# Motors-power-board.net
KiCad netlist of a schematic drawn in EAGLE
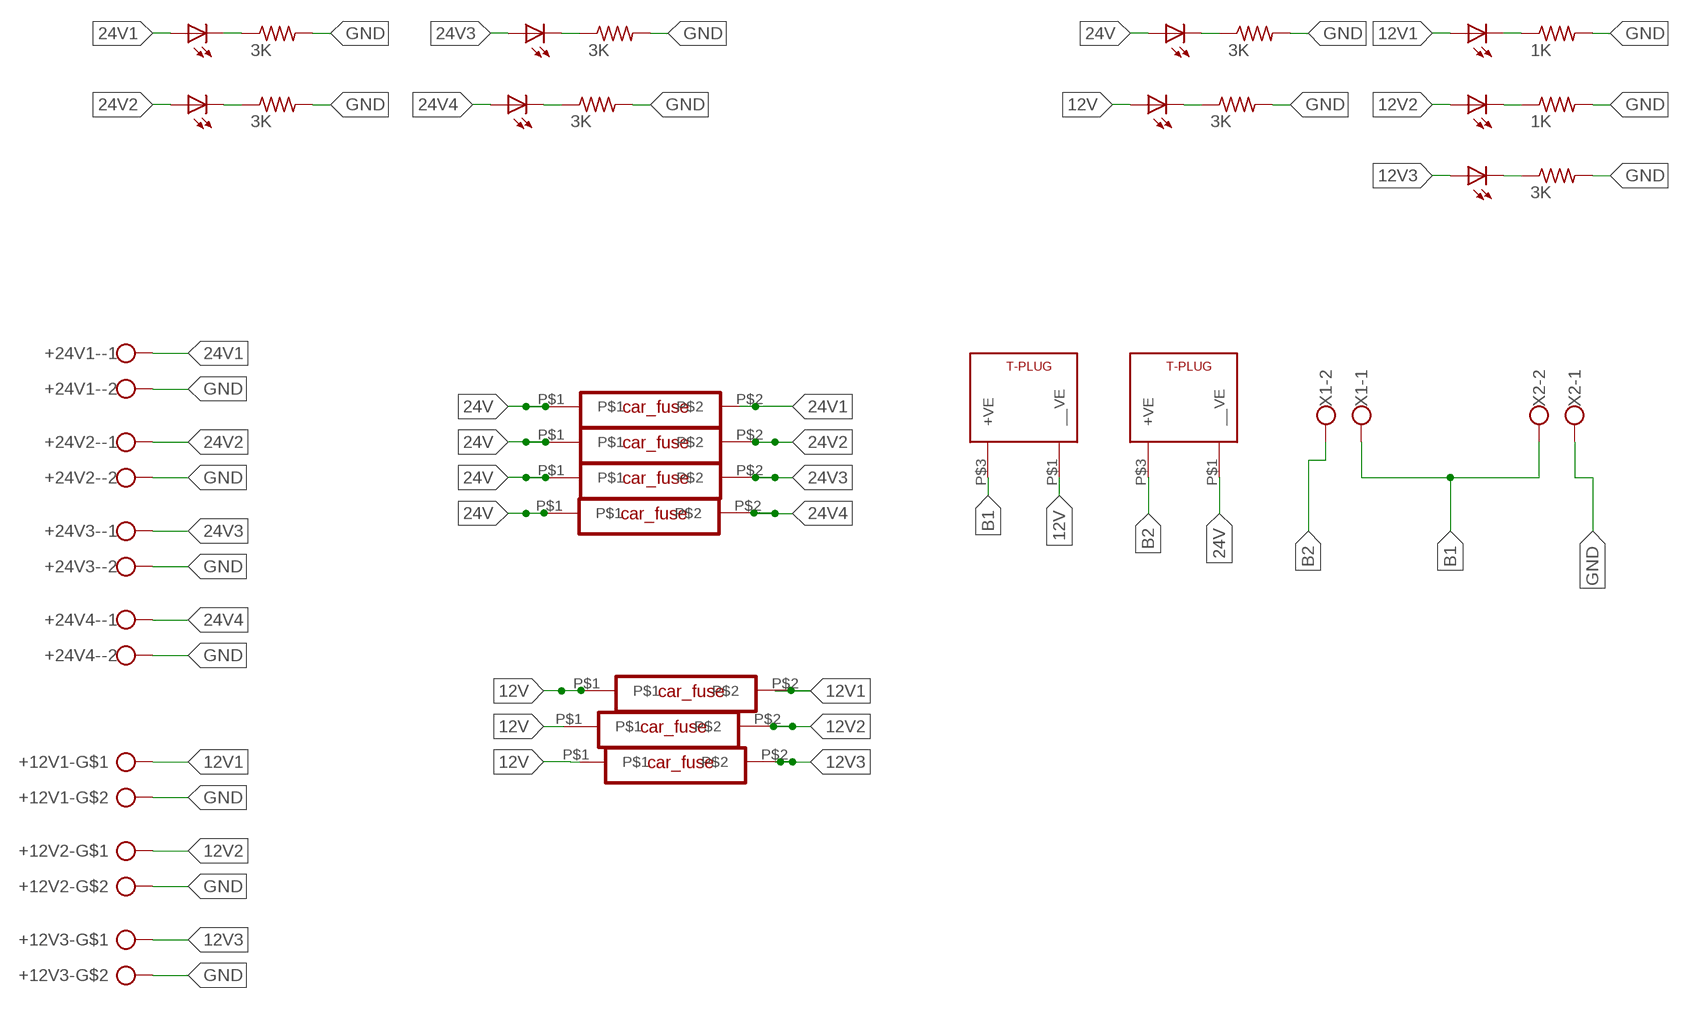
[diagram p0: schematic, sheet 1]

(export (version "E")
  (design (tool "Eeschema 10.0.6"))
  (components
    (comp (ref "+12V1-")
      (value "CON_PTR_2")
      (footprint "eagle-import:AK300_2")
      (libsource (lib "eagle-import") (part "CON_PTR_2"))
    )
    (comp (ref "+12V2-")
      (value "CON_PTR_2")
      (footprint "eagle-import:AK300_2")
      (libsource (lib "eagle-import") (part "CON_PTR_2"))
    )
    (comp (ref "+12V3-")
      (value "CON_PTR_2")
      (footprint "eagle-import:AK300_2")
      (libsource (lib "eagle-import") (part "CON_PTR_2"))
    )
    (comp (ref "+24V1-")
      (value "ROSTA.POWER")
      (footprint "eagle-import:W239-302")
      (libsource (lib "eagle-import") (part "ROSTA.POWER"))
    )
    (comp (ref "+24V2-")
      (value "ROSTA.POWER")
      (footprint "eagle-import:W239-302")
      (libsource (lib "eagle-import") (part "ROSTA.POWER"))
    )
    (comp (ref "+24V3-")
      (value "ROSTA.POWER")
      (footprint "eagle-import:W239-302")
      (libsource (lib "eagle-import") (part "ROSTA.POWER"))
    )
    (comp (ref "+24V4-")
      (value "ROSTA.POWER")
      (footprint "eagle-import:W239-302")
      (libsource (lib "eagle-import") (part "ROSTA.POWER"))
    )
    (comp (ref "1K1")
      (value "3K")
      (footprint "eagle-import:0204_7")
      (libsource (lib "eagle-import") (part "RES-7"))
    )
    (comp (ref "1K2")
      (value "1K")
      (footprint "eagle-import:0204_7")
      (libsource (lib "eagle-import") (part "RES-7"))
    )
    (comp (ref "U$4")
      (value "LED24V")
      (footprint "eagle-import:LED3MM")
      (libsource (lib "eagle-import") (part "LED3MM"))
    )
    (comp (ref "U$5")
      (value "T_CONNECTOR")
      (footprint "eagle-import:T-PLUG")
      (libsource (lib "eagle-import") (part "T_CONNECTOR"))
    )
    (comp (ref "U$6")
      (value "T_CONNECTOR")
      (footprint "eagle-import:T-PLUG")
      (libsource (lib "eagle-import") (part "T_CONNECTOR"))
    )
    (comp (ref "U$8")
      (value "3K")
      (footprint "eagle-import:0204_7")
      (libsource (lib "eagle-import") (part "RES-7"))
    )
    (comp (ref "U$9")
      (value "3K")
      (footprint "eagle-import:0204_7")
      (libsource (lib "eagle-import") (part "RES-7"))
    )
    (comp (ref "U$10")
      (value "CAR_FUSE")
      (footprint "eagle-import:CAR_FUSE")
      (libsource (lib "eagle-import") (part "CAR_FUSE"))
    )
    (comp (ref "U$11")
      (value "CAR_FUSE")
      (footprint "eagle-import:CAR_FUSE")
      (libsource (lib "eagle-import") (part "CAR_FUSE"))
    )
    (comp (ref "U$12")
      (value "CAR_FUSE")
      (footprint "eagle-import:CAR_FUSE")
      (libsource (lib "eagle-import") (part "CAR_FUSE"))
    )
    (comp (ref "U$13")
      (value "CAR_FUSE")
      (footprint "eagle-import:CAR_FUSE")
      (libsource (lib "eagle-import") (part "CAR_FUSE"))
    )
    (comp (ref "U$14")
      (value "CAR_FUSE")
      (footprint "eagle-import:CAR_FUSE")
      (libsource (lib "eagle-import") (part "CAR_FUSE"))
    )
    (comp (ref "U$15")
      (value "CAR_FUSE")
      (footprint "eagle-import:CAR_FUSE")
      (libsource (lib "eagle-import") (part "CAR_FUSE"))
    )
    (comp (ref "U$16")
      (value "CAR_FUSE")
      (footprint "eagle-import:CAR_FUSE")
      (libsource (lib "eagle-import") (part "CAR_FUSE"))
    )
    (comp (ref "U$18")
      (value "LED5V2")
      (footprint "eagle-import:LED3MM")
      (libsource (lib "eagle-import") (part "LED3MM"))
    )
    (comp (ref "U$19")
      (value "LED5V1")
      (footprint "eagle-import:LED3MM")
      (libsource (lib "eagle-import") (part "LED3MM"))
    )
    (comp (ref "U$20")
      (value "LED24V")
      (footprint "eagle-import:LED3MM")
      (libsource (lib "eagle-import") (part "LED3MM"))
    )
    (comp (ref "U$21")
      (value "LED12V")
      (footprint "eagle-import:LED3MM")
      (libsource (lib "eagle-import") (part "LED3MM"))
    )
    (comp (ref "U$22")
      (value "3K")
      (footprint "eagle-import:0204_7")
      (libsource (lib "eagle-import") (part "RES-7"))
    )
    (comp (ref "U$23")
      (value "3K")
      (footprint "eagle-import:0204_7")
      (libsource (lib "eagle-import") (part "RES-7"))
    )
    (comp (ref "U$24")
      (value "3K")
      (footprint "eagle-import:0204_7")
      (libsource (lib "eagle-import") (part "RES-7"))
    )
    (comp (ref "U$25")
      (value "LED5V2")
      (footprint "eagle-import:LED3MM")
      (libsource (lib "eagle-import") (part "LED3MM"))
    )
    (comp (ref "U$26")
      (value "LED5V1")
      (footprint "eagle-import:LED3MM")
      (libsource (lib "eagle-import") (part "LED3MM"))
    )
    (comp (ref "U$27")
      (value "LED24V")
      (footprint "eagle-import:LED3MM")
      (libsource (lib "eagle-import") (part "LED3MM"))
    )
    (comp (ref "U$28")
      (value "LED24V")
      (footprint "eagle-import:LED3MM")
      (libsource (lib "eagle-import") (part "LED3MM"))
    )
    (comp (ref "U$29")
      (value "1K")
      (footprint "eagle-import:0204_7")
      (libsource (lib "eagle-import") (part "RES-7"))
    )
    (comp (ref "U$31")
      (value "3K")
      (footprint "eagle-import:0204_7")
      (libsource (lib "eagle-import") (part "RES-7"))
    )
    (comp (ref "X1")
      (value "ROSTA.POWER")
      (footprint "eagle-import:W239-302")
      (libsource (lib "eagle-import") (part "MIA_LIBRARY-2-2-2_16672108_ROSTA.POWER"))
    )
    (comp (ref "X2")
      (value "ROSTA.POWER")
      (footprint "eagle-import:W239-302")
      (libsource (lib "eagle-import") (part "MIA_LIBRARY-2-2-2_16672108_ROSTA.POWER"))
    )
  )
  (nets
    (net (code "1") (name "12V") (class "Default")
      (node (ref "U$14") (pin "P$1") (pinfunction "P$1_P$1") (pintype "bidirectional"))
      (node (ref "U$15") (pin "P$1") (pinfunction "P$1_P$1") (pintype "bidirectional"))
      (node (ref "U$16") (pin "P$1") (pinfunction "P$1_P$1") (pintype "bidirectional"))
      (node (ref "U$28") (pin "A") (pinfunction "A_A") (pintype "passive"))
      (node (ref "U$5") (pin "P$1") (pinfunction "__VE_P$1") (pintype "bidirectional"))
    )
    (net (code "2") (name "12V1") (class "Default")
      (node (ref "+12V1-") (pin "1") (pinfunction "KL_1") (pintype "passive"))
      (node (ref "U$14") (pin "P$2") (pinfunction "P$2_P$2") (pintype "bidirectional"))
      (node (ref "U$25") (pin "A") (pinfunction "A_A") (pintype "passive"))
    )
    (net (code "3") (name "12V2") (class "Default")
      (node (ref "+12V2-") (pin "1") (pinfunction "KL_1") (pintype "passive"))
      (node (ref "U$15") (pin "P$2") (pinfunction "P$2_P$2") (pintype "bidirectional"))
      (node (ref "U$26") (pin "A") (pinfunction "A_A") (pintype "passive"))
    )
    (net (code "4") (name "12V3") (class "Default")
      (node (ref "+12V3-") (pin "1") (pinfunction "KL_1") (pintype "passive"))
      (node (ref "U$16") (pin "P$2") (pinfunction "P$2_P$2") (pintype "bidirectional"))
      (node (ref "U$27") (pin "A") (pinfunction "A_A") (pintype "passive"))
    )
    (net (code "5") (name "24V") (class "Default")
      (node (ref "U$10") (pin "P$1") (pinfunction "P$1_P$1") (pintype "bidirectional"))
      (node (ref "U$11") (pin "P$1") (pinfunction "P$1_P$1") (pintype "bidirectional"))
      (node (ref "U$12") (pin "P$1") (pinfunction "P$1_P$1") (pintype "bidirectional"))
      (node (ref "U$13") (pin "P$1") (pinfunction "P$1_P$1") (pintype "bidirectional"))
      (node (ref "U$4") (pin "A") (pinfunction "A_A") (pintype "passive"))
      (node (ref "U$6") (pin "P$1") (pinfunction "__VE_P$1") (pintype "bidirectional"))
    )
    (net (code "6") (name "24V1") (class "Default")
      (node (ref "+24V1-") (pin "1") (pinfunction "KL_1") (pintype "passive"))
      (node (ref "U$10") (pin "P$2") (pinfunction "P$2_P$2") (pintype "bidirectional"))
      (node (ref "U$18") (pin "A") (pinfunction "A_A") (pintype "passive"))
    )
    (net (code "7") (name "24V2") (class "Default")
      (node (ref "+24V2-") (pin "1") (pinfunction "KL_1") (pintype "passive"))
      (node (ref "U$11") (pin "P$2") (pinfunction "P$2_P$2") (pintype "bidirectional"))
      (node (ref "U$19") (pin "A") (pinfunction "A_A") (pintype "passive"))
    )
    (net (code "8") (name "24V3") (class "Default")
      (node (ref "+24V3-") (pin "1") (pinfunction "KL_1") (pintype "passive"))
      (node (ref "U$12") (pin "P$2") (pinfunction "P$2_P$2") (pintype "bidirectional"))
      (node (ref "U$20") (pin "A") (pinfunction "A_A") (pintype "passive"))
    )
    (net (code "9") (name "24V4") (class "Default")
      (node (ref "+24V4-") (pin "1") (pinfunction "KL_1") (pintype "passive"))
      (node (ref "U$13") (pin "P$2") (pinfunction "P$2_P$2") (pintype "bidirectional"))
      (node (ref "U$21") (pin "A") (pinfunction "A_A") (pintype "passive"))
    )
    (net (code "10") (name "B1") (class "Default")
      (node (ref "U$5") (pin "P$3") (pinfunction "+VE_P$3") (pintype "bidirectional"))
      (node (ref "X1") (pin "1") (pinfunction "KL_1") (pintype "passive"))
      (node (ref "X2") (pin "2") (pinfunction "KL_2") (pintype "passive"))
    )
    (net (code "11") (name "B2") (class "Default")
      (node (ref "U$6") (pin "P$3") (pinfunction "+VE_P$3") (pintype "bidirectional"))
      (node (ref "X1") (pin "2") (pinfunction "KL_2") (pintype "passive"))
    )
    (net (code "12") (name "GND") (class "Default")
      (node (ref "+12V1-") (pin "2") (pinfunction "KL_2") (pintype "passive"))
      (node (ref "+12V2-") (pin "2") (pinfunction "KL_2") (pintype "passive"))
      (node (ref "+12V3-") (pin "2") (pinfunction "KL_2") (pintype "passive"))
      (node (ref "+24V1-") (pin "2") (pinfunction "KL_2") (pintype "passive"))
      (node (ref "+24V2-") (pin "2") (pinfunction "KL_2") (pintype "passive"))
      (node (ref "+24V3-") (pin "2") (pinfunction "KL_2") (pintype "passive"))
      (node (ref "+24V4-") (pin "2") (pinfunction "KL_2") (pintype "passive"))
      (node (ref "1K1") (pin "2") (pinfunction "2_2") (pintype "passive"))
      (node (ref "1K2") (pin "2") (pinfunction "2_2") (pintype "passive"))
      (node (ref "U$22") (pin "2") (pinfunction "2_2") (pintype "passive"))
      (node (ref "U$23") (pin "2") (pinfunction "2_2") (pintype "passive"))
      (node (ref "U$24") (pin "2") (pinfunction "2_2") (pintype "passive"))
      (node (ref "U$29") (pin "2") (pinfunction "2_2") (pintype "passive"))
      (node (ref "U$31") (pin "2") (pinfunction "2_2") (pintype "passive"))
      (node (ref "U$8") (pin "2") (pinfunction "2_2") (pintype "passive"))
      (node (ref "U$9") (pin "2") (pinfunction "2_2") (pintype "passive"))
      (node (ref "X2") (pin "1") (pinfunction "KL_1") (pintype "passive"))
    )
    (net (code "13") (name "Net-(U$4-C)") (class "Default")
      (node (ref "U$4") (pin "K") (pinfunction "C_K") (pintype "passive"))
      (node (ref "U$9") (pin "1") (pinfunction "1_1") (pintype "passive"))
    )
    (net (code "14") (name "Net-(U$18-C)") (class "Default")
      (node (ref "1K1") (pin "1") (pinfunction "1_1") (pintype "passive"))
      (node (ref "U$18") (pin "K") (pinfunction "C_K") (pintype "passive"))
    )
    (net (code "15") (name "Net-(U$19-C)") (class "Default")
      (node (ref "U$19") (pin "K") (pinfunction "C_K") (pintype "passive"))
      (node (ref "U$22") (pin "1") (pinfunction "1_1") (pintype "passive"))
    )
    (net (code "16") (name "Net-(U$20-C)") (class "Default")
      (node (ref "U$20") (pin "K") (pinfunction "C_K") (pintype "passive"))
      (node (ref "U$24") (pin "1") (pinfunction "1_1") (pintype "passive"))
    )
    (net (code "17") (name "Net-(U$21-C)") (class "Default")
      (node (ref "U$21") (pin "K") (pinfunction "C_K") (pintype "passive"))
      (node (ref "U$23") (pin "1") (pinfunction "1_1") (pintype "passive"))
    )
    (net (code "18") (name "Net-(U$25-C)") (class "Default")
      (node (ref "1K2") (pin "1") (pinfunction "1_1") (pintype "passive"))
      (node (ref "U$25") (pin "K") (pinfunction "C_K") (pintype "passive"))
    )
    (net (code "19") (name "Net-(U$26-C)") (class "Default")
      (node (ref "U$26") (pin "K") (pinfunction "C_K") (pintype "passive"))
      (node (ref "U$29") (pin "1") (pinfunction "1_1") (pintype "passive"))
    )
    (net (code "20") (name "Net-(U$27-C)") (class "Default")
      (node (ref "U$27") (pin "K") (pinfunction "C_K") (pintype "passive"))
      (node (ref "U$31") (pin "1") (pinfunction "1_1") (pintype "passive"))
    )
    (net (code "21") (name "Net-(U$28-C)") (class "Default")
      (node (ref "U$28") (pin "K") (pinfunction "C_K") (pintype "passive"))
      (node (ref "U$8") (pin "1") (pinfunction "1_1") (pintype "passive"))
    )
  )
)
